# Hi_Current.net
KiCad netlist of a schematic drawn in Altium Designer
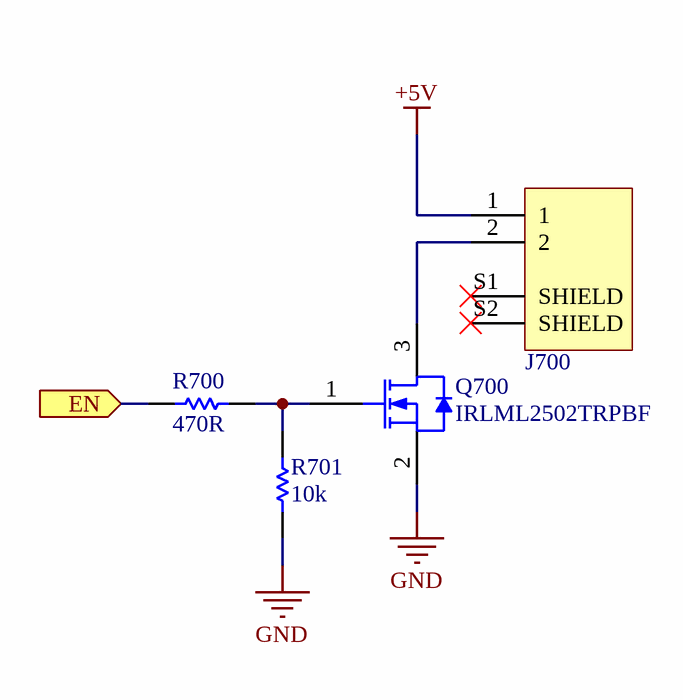
[diagram p0: Hi_Current.SchDoc]

(export (version "E")
  (design (tool "Eeschema 10.0.6"))
  (components
    (comp (ref "J700")
      (value "2 pin vertical JST GH")
      (footprint "JST_BM02B-GHS-TBT(LF)(SN)(N)")
      (description "JST GH vertical 2 pin\r\nDigiKey part no. 455-1578-1-ND")
      (fields (field (name "MF") "JST Sales") (field (name "DIGI-KEY_PART_NUMBER") "455-1580-1-ND"))
      (libsource (lib "Moonlight_Components") (part "BM02B-GHS-TBT(LF)(SN)(N)"))
    )
    (comp (ref "Q700")
      (value "IRLML2502TRPBF")
      (footprint "INTR-SOT-23-3_V")
      (description "N-Channel HEXFET(R) Power MOSFET, 20 V VDS, +/- 12 V VGS, 4.2 A, 3-Pin SOT23, RoHS, Tape and Reel")
      (fields (field (name "MANUFACTURER") "International Rectifier"))
      (libsource (lib "Moonlight_Components") (part "IRLML2502TRPBF"))
    )
    (comp (ref "R700")
      (value "470R")
      (footprint "0603_RES")
      (libsource (lib "Moonlight-Components") (part "Resistor"))
    )
    (comp (ref "R701")
      (value "10k")
      (footprint "0603_RES")
      (libsource (lib "Moonlight-Components") (part "Resistor"))
    )
  )
  (nets
    (net (code "1") (name "+5V") (class "Default")
      (node (ref "J700") (pin "1") (pinfunction "1_1") (pintype "passive"))
    )
    (net (code "2") (name "/EN") (class "Default")
      (node (ref "R700") (pin "1") (pinfunction "1_1") (pintype "passive"))
    )
    (net (code "3") (name "GND") (class "Default")
      (node (ref "Q700") (pin "2") (pinfunction "S_2") (pintype "passive"))
      (node (ref "R701") (pin "2") (pinfunction "2_2") (pintype "passive"))
    )
    (net (code "4") (name "Net-(Q700-D)") (class "Default")
      (node (ref "J700") (pin "2") (pinfunction "2_2") (pintype "passive"))
      (node (ref "Q700") (pin "3") (pinfunction "D_3") (pintype "passive"))
    )
    (net (code "5") (name "Net-(Q700-G)") (class "Default")
      (node (ref "Q700") (pin "1") (pinfunction "G_1") (pintype "passive"))
      (node (ref "R700") (pin "2") (pinfunction "2_2") (pintype "passive"))
      (node (ref "R701") (pin "1") (pinfunction "1_1") (pintype "passive"))
    )
    (net (code "6") (name "unconnected-(J700-SHIELD-PadS1)") (class "Default")
      (node (ref "J700") (pin "S1") (pinfunction "SHIELD_S1") (pintype "passive+no_connect"))
    )
    (net (code "7") (name "unconnected-(J700-SHIELD-PadS2)") (class "Default")
      (node (ref "J700") (pin "S2") (pinfunction "SHIELD_S2") (pintype "passive+no_connect"))
    )
  )
)
